# B_Bot_Cube.net
KiCad netlist of a schematic drawn in EAGLE
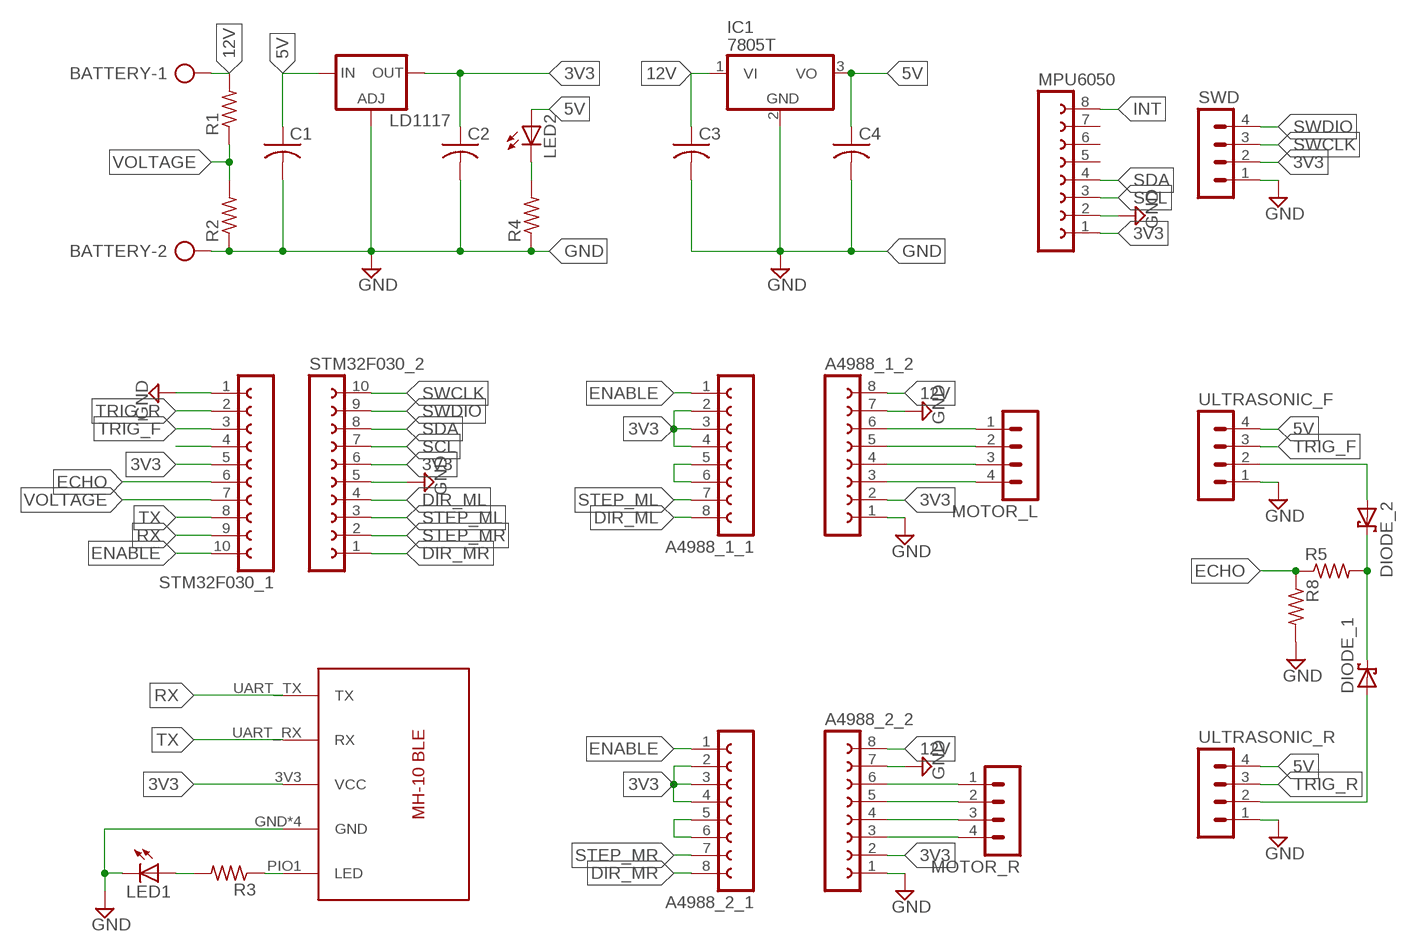
[diagram p0: schematic, sheet 1]

(export (version "E")
  (design (tool "Eeschema 10.0.6"))
  (components
    (comp (ref "A4988_1_1")
      (value "FE08-1")
      (footprint "eagle-import:FE08")
      (libsource (lib "eagle-import") (part "FE08-1"))
    )
    (comp (ref "A4988_1_2")
      (value "FE08-1")
      (footprint "eagle-import:FE08")
      (libsource (lib "eagle-import") (part "FE08-1"))
    )
    (comp (ref "A4988_2_1")
      (value "FE08-1")
      (footprint "eagle-import:FE08")
      (libsource (lib "eagle-import") (part "FE08-1"))
    )
    (comp (ref "A4988_2_2")
      (value "FE08-1")
      (footprint "eagle-import:FE08")
      (libsource (lib "eagle-import") (part "FE08-1"))
    )
    (comp (ref "BATTERY")
      (value "AK500/2")
      (footprint "eagle-import:AK500_2")
      (libsource (lib "eagle-import") (part "AK500/2"))
    )
    (comp (ref "C1")
      (value "C-USC0805K")
      (footprint "eagle-import:C0805K")
      (libsource (lib "eagle-import") (part "C-USC0805K"))
    )
    (comp (ref "C2")
      (value "C-USC0805K")
      (footprint "eagle-import:C0805K")
      (libsource (lib "eagle-import") (part "C-USC0805K"))
    )
    (comp (ref "C3")
      (value "C-USC0805K")
      (footprint "eagle-import:C0805K")
      (libsource (lib "eagle-import") (part "C-USC0805K"))
    )
    (comp (ref "C4")
      (value "C-USC0805K")
      (footprint "eagle-import:C0805K")
      (libsource (lib "eagle-import") (part "C-USC0805K"))
    )
    (comp (ref "DIODE_1")
      (value "BAT60J")
      (footprint "eagle-import:SOD323_ST")
      (libsource (lib "eagle-import") (part "BAT60J"))
    )
    (comp (ref "DIODE_2")
      (value "BAT60J")
      (footprint "eagle-import:SOD323_ST")
      (libsource (lib "eagle-import") (part "BAT60J"))
    )
    (comp (ref "IC1")
      (value "7805T")
      (footprint "eagle-import:TO220H")
      (libsource (lib "eagle-import") (part "78T05"))
    )
    (comp (ref "LD1117")
      (value "LD117AS33TR")
      (footprint "eagle-import:SOT223")
      (libsource (lib "eagle-import") (part "LD117A?S33TR"))
    )
    (comp (ref "LED1")
      (value "LED-0805")
      (footprint "eagle-import:LED-805")
      (libsource (lib "eagle-import") (part "LED-0805"))
    )
    (comp (ref "LED2")
      (value "LED-0805")
      (footprint "eagle-import:LED-805")
      (libsource (lib "eagle-import") (part "LED-0805"))
    )
    (comp (ref "MOTOR_L")
      (value "MA04-1")
      (footprint "eagle-import:MA04-1")
      (libsource (lib "eagle-import") (part "MA04-1"))
    )
    (comp (ref "MOTOR_R")
      (value "MA04-1")
      (footprint "eagle-import:MA04-1")
      (libsource (lib "eagle-import") (part "MA04-1"))
    )
    (comp (ref "MPU6050")
      (value "FE08-1")
      (footprint "eagle-import:FE08")
      (libsource (lib "eagle-import") (part "FE08-1"))
    )
    (comp (ref "R1")
      (value "R-US_M0805")
      (footprint "eagle-import:M0805")
      (libsource (lib "eagle-import") (part "R-US_M0805"))
    )
    (comp (ref "R2")
      (value "R-US_M0805")
      (footprint "eagle-import:M0805")
      (libsource (lib "eagle-import") (part "R-US_M0805"))
    )
    (comp (ref "R3")
      (value "R-US_M0805")
      (footprint "eagle-import:M0805")
      (libsource (lib "eagle-import") (part "R-US_M0805"))
    )
    (comp (ref "R4")
      (value "R-US_M0805")
      (footprint "eagle-import:M0805")
      (libsource (lib "eagle-import") (part "R-US_M0805"))
    )
    (comp (ref "R5")
      (value "R-US_M0805")
      (footprint "eagle-import:M0805")
      (libsource (lib "eagle-import") (part "R-US_M0805"))
    )
    (comp (ref "R8")
      (value "R-US_M0805")
      (footprint "eagle-import:M0805")
      (libsource (lib "eagle-import") (part "R-US_M0805"))
    )
    (comp (ref "STM32F030_1")
      (value "FE10-1")
      (footprint "eagle-import:FE10")
      (libsource (lib "eagle-import") (part "FE10-1"))
    )
    (comp (ref "STM32F030_2")
      (value "FE10-1")
      (footprint "eagle-import:FE10")
      (libsource (lib "eagle-import") (part "FE10-1"))
    )
    (comp (ref "SWD")
      (value "MA04-1")
      (footprint "eagle-import:MA04-1")
      (libsource (lib "eagle-import") (part "MA04-1"))
    )
    (comp (ref "U$1")
      (value "HM-10")
      (footprint "eagle-import:HM-10")
      (libsource (lib "eagle-import") (part "HM-10"))
    )
    (comp (ref "ULTRASONIC_F")
      (value "MA04-1")
      (footprint "eagle-import:MA04-1")
      (libsource (lib "eagle-import") (part "MA04-1"))
    )
    (comp (ref "ULTRASONIC_R")
      (value "MA04-1")
      (footprint "eagle-import:MA04-1")
      (libsource (lib "eagle-import") (part "MA04-1"))
    )
  )
  (nets
    (net (code "1") (name "3V3") (class "Default")
      (node (ref "A4988_1_1") (pin "2") (pinfunction "2_2") (pintype "passive"))
      (node (ref "A4988_1_1") (pin "3") (pinfunction "3_3") (pintype "passive"))
      (node (ref "A4988_1_1") (pin "4") (pinfunction "4_4") (pintype "passive"))
      (node (ref "A4988_1_2") (pin "2") (pinfunction "2_2") (pintype "passive"))
      (node (ref "A4988_2_1") (pin "2") (pinfunction "2_2") (pintype "passive"))
      (node (ref "A4988_2_1") (pin "3") (pinfunction "3_3") (pintype "passive"))
      (node (ref "A4988_2_1") (pin "4") (pinfunction "4_4") (pintype "passive"))
      (node (ref "A4988_2_2") (pin "2") (pinfunction "2_2") (pintype "passive"))
      (node (ref "C2") (pin "1") (pinfunction "1_1") (pintype "passive"))
      (node (ref "LD1117") (pin "4") (pinfunction "OUT_4") (pintype "passive"))
      (node (ref "MPU6050") (pin "1") (pinfunction "1_1") (pintype "passive"))
      (node (ref "STM32F030_1") (pin "5") (pinfunction "5_5") (pintype "passive"))
      (node (ref "STM32F030_2") (pin "6") (pinfunction "6_6") (pintype "passive"))
      (node (ref "SWD") (pin "2") (pinfunction "2_2") (pintype "passive"))
      (node (ref "U$1") (pin "3V3") (pinfunction "VCC_3V3") (pintype "bidirectional"))
    )
    (net (code "2") (name "5V") (class "Default")
      (node (ref "C1") (pin "1") (pinfunction "1_1") (pintype "passive"))
      (node (ref "C4") (pin "1") (pinfunction "1_1") (pintype "passive"))
      (node (ref "IC1") (pin "3") (pinfunction "VO_3") (pintype "passive"))
      (node (ref "LD1117") (pin "3") (pinfunction "IN_3") (pintype "input"))
      (node (ref "LED2") (pin "A") (pinfunction "A_A") (pintype "passive"))
      (node (ref "ULTRASONIC_F") (pin "4") (pinfunction "4_4") (pintype "passive"))
      (node (ref "ULTRASONIC_R") (pin "4") (pinfunction "4_4") (pintype "passive"))
    )
    (net (code "3") (name "12V") (class "Default")
      (node (ref "A4988_1_2") (pin "8") (pinfunction "8_8") (pintype "passive"))
      (node (ref "A4988_2_2") (pin "8") (pinfunction "8_8") (pintype "passive"))
      (node (ref "BATTERY") (pin "1") (pinfunction "KL_1") (pintype "passive"))
      (node (ref "C3") (pin "1") (pinfunction "1_1") (pintype "passive"))
      (node (ref "IC1") (pin "1") (pinfunction "VI_1") (pintype "input"))
      (node (ref "R1") (pin "2") (pinfunction "2_2") (pintype "passive"))
    )
    (net (code "4") (name "DIR_ML") (class "Default")
      (node (ref "A4988_1_1") (pin "8") (pinfunction "8_8") (pintype "passive"))
      (node (ref "STM32F030_2") (pin "4") (pinfunction "4_4") (pintype "passive"))
    )
    (net (code "5") (name "DIR_MR") (class "Default")
      (node (ref "A4988_2_1") (pin "8") (pinfunction "8_8") (pintype "passive"))
      (node (ref "STM32F030_2") (pin "1") (pinfunction "1_1") (pintype "passive"))
    )
    (net (code "6") (name "ECHO") (class "Default")
      (node (ref "R5") (pin "1") (pinfunction "1_1") (pintype "passive"))
      (node (ref "R8") (pin "1") (pinfunction "1_1") (pintype "passive"))
      (node (ref "STM32F030_1") (pin "6") (pinfunction "6_6") (pintype "passive"))
    )
    (net (code "7") (name "ENABLE") (class "Default")
      (node (ref "A4988_1_1") (pin "1") (pinfunction "1_1") (pintype "passive"))
      (node (ref "A4988_2_1") (pin "1") (pinfunction "1_1") (pintype "passive"))
      (node (ref "STM32F030_1") (pin "10") (pinfunction "10_10") (pintype "passive"))
    )
    (net (code "8") (name "GND") (class "Default")
      (node (ref "A4988_1_2") (pin "1") (pinfunction "1_1") (pintype "passive"))
      (node (ref "A4988_1_2") (pin "7") (pinfunction "7_7") (pintype "passive"))
      (node (ref "A4988_2_2") (pin "1") (pinfunction "1_1") (pintype "passive"))
      (node (ref "A4988_2_2") (pin "7") (pinfunction "7_7") (pintype "passive"))
      (node (ref "BATTERY") (pin "2") (pinfunction "KL_2") (pintype "passive"))
      (node (ref "C1") (pin "2") (pinfunction "2_2") (pintype "passive"))
      (node (ref "C2") (pin "2") (pinfunction "2_2") (pintype "passive"))
      (node (ref "C3") (pin "2") (pinfunction "2_2") (pintype "passive"))
      (node (ref "C4") (pin "2") (pinfunction "2_2") (pintype "passive"))
      (node (ref "IC1") (pin "2") (pinfunction "GND_2") (pintype "passive"))
      (node (ref "LD1117") (pin "1") (pinfunction "ADJ_1") (pintype "input"))
      (node (ref "LED1") (pin "C") (pinfunction "C_C") (pintype "passive"))
      (node (ref "MPU6050") (pin "2") (pinfunction "2_2") (pintype "passive"))
      (node (ref "R2") (pin "1") (pinfunction "1_1") (pintype "passive"))
      (node (ref "R4") (pin "1") (pinfunction "1_1") (pintype "passive"))
      (node (ref "R8") (pin "2") (pinfunction "2_2") (pintype "passive"))
      (node (ref "STM32F030_1") (pin "1") (pinfunction "1_1") (pintype "passive"))
      (node (ref "STM32F030_2") (pin "5") (pinfunction "5_5") (pintype "passive"))
      (node (ref "SWD") (pin "1") (pinfunction "1_1") (pintype "passive"))
      (node (ref "U$1") (pin "GND") (pinfunction "GND_GND") (pintype "bidirectional"))
      (node (ref "U$1") (pin "GND2") (pinfunction "GND_GND2") (pintype "bidirectional"))
      (node (ref "U$1") (pin "GND3") (pinfunction "GND_GND3") (pintype "bidirectional"))
      (node (ref "U$1") (pin "GND4") (pinfunction "GND_GND4") (pintype "bidirectional"))
      (node (ref "ULTRASONIC_F") (pin "1") (pinfunction "1_1") (pintype "passive"))
      (node (ref "ULTRASONIC_R") (pin "1") (pinfunction "1_1") (pintype "passive"))
    )
    (net (code "9") (name "INT") (class "Default")
      (node (ref "MPU6050") (pin "8") (pinfunction "8_8") (pintype "passive"))
    )
    (net (code "10") (name "Net-(A4988_1_1-Pad5)") (class "Default")
      (node (ref "A4988_1_1") (pin "5") (pinfunction "5_5") (pintype "passive"))
      (node (ref "A4988_1_1") (pin "6") (pinfunction "6_6") (pintype "passive"))
    )
    (net (code "11") (name "Net-(A4988_1_2-Pad3)") (class "Default")
      (node (ref "A4988_1_2") (pin "3") (pinfunction "3_3") (pintype "passive"))
      (node (ref "MOTOR_L") (pin "4") (pinfunction "4_4") (pintype "passive"))
    )
    (net (code "12") (name "Net-(A4988_1_2-Pad4)") (class "Default")
      (node (ref "A4988_1_2") (pin "4") (pinfunction "4_4") (pintype "passive"))
      (node (ref "MOTOR_L") (pin "3") (pinfunction "3_3") (pintype "passive"))
    )
    (net (code "13") (name "Net-(A4988_1_2-Pad5)") (class "Default")
      (node (ref "A4988_1_2") (pin "5") (pinfunction "5_5") (pintype "passive"))
      (node (ref "MOTOR_L") (pin "2") (pinfunction "2_2") (pintype "passive"))
    )
    (net (code "14") (name "Net-(A4988_1_2-Pad6)") (class "Default")
      (node (ref "A4988_1_2") (pin "6") (pinfunction "6_6") (pintype "passive"))
      (node (ref "MOTOR_L") (pin "1") (pinfunction "1_1") (pintype "passive"))
    )
    (net (code "15") (name "Net-(A4988_2_1-Pad5)") (class "Default")
      (node (ref "A4988_2_1") (pin "5") (pinfunction "5_5") (pintype "passive"))
      (node (ref "A4988_2_1") (pin "6") (pinfunction "6_6") (pintype "passive"))
    )
    (net (code "16") (name "Net-(A4988_2_2-Pad3)") (class "Default")
      (node (ref "A4988_2_2") (pin "3") (pinfunction "3_3") (pintype "passive"))
      (node (ref "MOTOR_R") (pin "4") (pinfunction "4_4") (pintype "passive"))
    )
    (net (code "17") (name "Net-(A4988_2_2-Pad4)") (class "Default")
      (node (ref "A4988_2_2") (pin "4") (pinfunction "4_4") (pintype "passive"))
      (node (ref "MOTOR_R") (pin "3") (pinfunction "3_3") (pintype "passive"))
    )
    (net (code "18") (name "Net-(A4988_2_2-Pad5)") (class "Default")
      (node (ref "A4988_2_2") (pin "5") (pinfunction "5_5") (pintype "passive"))
      (node (ref "MOTOR_R") (pin "2") (pinfunction "2_2") (pintype "passive"))
    )
    (net (code "19") (name "Net-(A4988_2_2-Pad6)") (class "Default")
      (node (ref "A4988_2_2") (pin "6") (pinfunction "6_6") (pintype "passive"))
      (node (ref "MOTOR_R") (pin "1") (pinfunction "1_1") (pintype "passive"))
    )
    (net (code "20") (name "Net-(DIODE_1-PadA)") (class "Default")
      (node (ref "DIODE_1") (pin "A") (pinfunction "A_A") (pintype "passive"))
      (node (ref "ULTRASONIC_R") (pin "2") (pinfunction "2_2") (pintype "passive"))
    )
    (net (code "21") (name "Net-(DIODE_1-PadC)") (class "Default")
      (node (ref "DIODE_1") (pin "C") (pinfunction "C_C") (pintype "passive"))
      (node (ref "DIODE_2") (pin "C") (pinfunction "C_C") (pintype "passive"))
      (node (ref "R5") (pin "2") (pinfunction "2_2") (pintype "passive"))
    )
    (net (code "22") (name "Net-(DIODE_2-PadA)") (class "Default")
      (node (ref "DIODE_2") (pin "A") (pinfunction "A_A") (pintype "passive"))
      (node (ref "ULTRASONIC_F") (pin "2") (pinfunction "2_2") (pintype "passive"))
    )
    (net (code "23") (name "Net-(LED1-PadA)") (class "Default")
      (node (ref "LED1") (pin "A") (pinfunction "A_A") (pintype "passive"))
      (node (ref "R3") (pin "2") (pinfunction "2_2") (pintype "passive"))
    )
    (net (code "24") (name "Net-(LED2-PadC)") (class "Default")
      (node (ref "LED2") (pin "C") (pinfunction "C_C") (pintype "passive"))
      (node (ref "R4") (pin "2") (pinfunction "2_2") (pintype "passive"))
    )
    (net (code "25") (name "Net-(U$1-LED)") (class "Default")
      (node (ref "R3") (pin "1") (pinfunction "1_1") (pintype "passive"))
      (node (ref "U$1") (pin "PIO1") (pinfunction "LED_PIO1") (pintype "bidirectional"))
    )
    (net (code "26") (name "RX") (class "Default")
      (node (ref "STM32F030_1") (pin "9") (pinfunction "9_9") (pintype "passive"))
      (node (ref "U$1") (pin "UART_TX") (pinfunction "TX_UART_TX") (pintype "bidirectional"))
    )
    (net (code "27") (name "SCL") (class "Default")
      (node (ref "MPU6050") (pin "3") (pinfunction "3_3") (pintype "passive"))
      (node (ref "STM32F030_2") (pin "7") (pinfunction "7_7") (pintype "passive"))
    )
    (net (code "28") (name "SDA") (class "Default")
      (node (ref "MPU6050") (pin "4") (pinfunction "4_4") (pintype "passive"))
      (node (ref "STM32F030_2") (pin "8") (pinfunction "8_8") (pintype "passive"))
    )
    (net (code "29") (name "STEP_ML") (class "Default")
      (node (ref "A4988_1_1") (pin "7") (pinfunction "7_7") (pintype "passive"))
      (node (ref "STM32F030_2") (pin "3") (pinfunction "3_3") (pintype "passive"))
    )
    (net (code "30") (name "STEP_MR") (class "Default")
      (node (ref "A4988_2_1") (pin "7") (pinfunction "7_7") (pintype "passive"))
      (node (ref "STM32F030_2") (pin "2") (pinfunction "2_2") (pintype "passive"))
    )
    (net (code "31") (name "SWCLK") (class "Default")
      (node (ref "STM32F030_2") (pin "10") (pinfunction "10_10") (pintype "passive"))
      (node (ref "SWD") (pin "3") (pinfunction "3_3") (pintype "passive"))
    )
    (net (code "32") (name "SWDIO") (class "Default")
      (node (ref "STM32F030_2") (pin "9") (pinfunction "9_9") (pintype "passive"))
      (node (ref "SWD") (pin "4") (pinfunction "4_4") (pintype "passive"))
    )
    (net (code "33") (name "TRIG_F") (class "Default")
      (node (ref "STM32F030_1") (pin "3") (pinfunction "3_3") (pintype "passive"))
      (node (ref "ULTRASONIC_F") (pin "3") (pinfunction "3_3") (pintype "passive"))
    )
    (net (code "34") (name "TRIG_R") (class "Default")
      (node (ref "STM32F030_1") (pin "2") (pinfunction "2_2") (pintype "passive"))
      (node (ref "ULTRASONIC_R") (pin "3") (pinfunction "3_3") (pintype "passive"))
    )
    (net (code "35") (name "TX") (class "Default")
      (node (ref "STM32F030_1") (pin "8") (pinfunction "8_8") (pintype "passive"))
      (node (ref "U$1") (pin "UART_RX") (pinfunction "RX_UART_RX") (pintype "bidirectional"))
    )
    (net (code "36") (name "VOLTAGE") (class "Default")
      (node (ref "R1") (pin "1") (pinfunction "1_1") (pintype "passive"))
      (node (ref "R2") (pin "2") (pinfunction "2_2") (pintype "passive"))
      (node (ref "STM32F030_1") (pin "7") (pinfunction "7_7") (pintype "passive"))
    )
    (net (code "37") (name "unconnected-(MPU6050-Pad5)") (class "Default")
      (node (ref "MPU6050") (pin "5") (pinfunction "5_5") (pintype "passive"))
    )
    (net (code "38") (name "unconnected-(MPU6050-Pad6)") (class "Default")
      (node (ref "MPU6050") (pin "6") (pinfunction "6_6") (pintype "passive"))
    )
    (net (code "39") (name "unconnected-(MPU6050-Pad7)") (class "Default")
      (node (ref "MPU6050") (pin "7") (pinfunction "7_7") (pintype "passive"))
    )
    (net (code "40") (name "unconnected-(STM32F030_1-Pad4)") (class "Default")
      (node (ref "STM32F030_1") (pin "4") (pinfunction "4_4") (pintype "passive"))
    )
  )
)
